# k26_baseboard_dp.net
KiCad netlist of a schematic drawn in Altium Designer
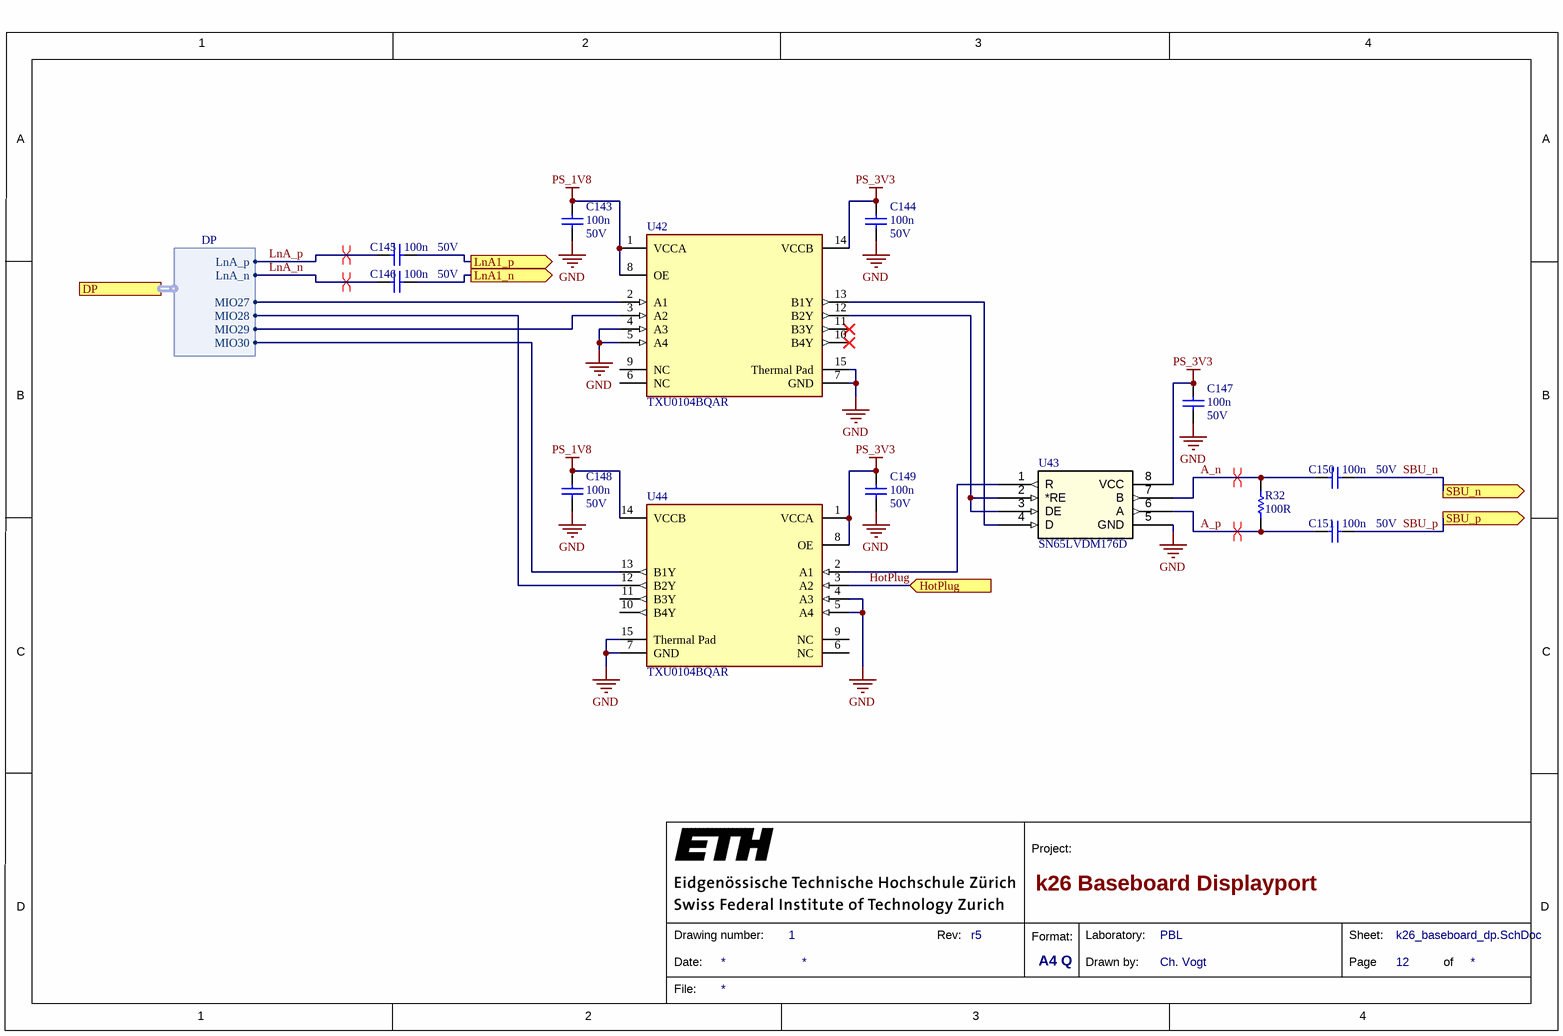
[diagram p0: k26_baseboard_dp.SchDoc]

(export (version "E")
  (design (tool "Eeschema 10.0.6"))
  (components
    (comp (ref "C143")
      (value "100n")
      (footprint "k26_FPGA_drone_baseboard:CAPC0402")
      (fields
        (field (name "MANUFACTURER") "Yageo")
        (field (name "MANUFACTURER PART NUMBER") "CC0402KRX5R9BB104")
        (field (name "RATED DC VOLTAGE (URDC)") "50V")
      )
      (libsource (lib "k26_FPGA_drone_baseboard") (part "cap0402"))
    )
    (comp (ref "C144")
      (value "100n")
      (footprint "k26_FPGA_drone_baseboard:CAPC0402")
      (fields
        (field (name "MANUFACTURER") "Yageo")
        (field (name "MANUFACTURER PART NUMBER") "CC0402KRX5R9BB104")
        (field (name "RATED DC VOLTAGE (URDC)") "50V")
      )
      (libsource (lib "k26_FPGA_drone_baseboard") (part "cap0402"))
    )
    (comp (ref "C145")
      (value "100n")
      (footprint "k26_FPGA_drone_baseboard:CAPC0402")
      (fields
        (field (name "MANUFACTURER") "Yageo")
        (field (name "MANUFACTURER PART NUMBER") "CC0402KRX5R9BB104")
        (field (name "RATED DC VOLTAGE (URDC)") "50V")
      )
      (libsource (lib "k26_FPGA_drone_baseboard") (part "cap0402"))
    )
    (comp (ref "C146")
      (value "100n")
      (footprint "k26_FPGA_drone_baseboard:CAPC0402")
      (fields
        (field (name "MANUFACTURER") "Yageo")
        (field (name "MANUFACTURER PART NUMBER") "CC0402KRX5R9BB104")
        (field (name "RATED DC VOLTAGE (URDC)") "50V")
      )
      (libsource (lib "k26_FPGA_drone_baseboard") (part "cap0402"))
    )
    (comp (ref "C147")
      (value "100n")
      (footprint "k26_FPGA_drone_baseboard:CAPC0402")
      (fields
        (field (name "MANUFACTURER") "Yageo")
        (field (name "MANUFACTURER PART NUMBER") "CC0402KRX5R9BB104")
        (field (name "RATED DC VOLTAGE (URDC)") "50V")
      )
      (libsource (lib "k26_FPGA_drone_baseboard") (part "cap0402"))
    )
    (comp (ref "C148")
      (value "100n")
      (footprint "k26_FPGA_drone_baseboard:CAPC0402")
      (fields
        (field (name "MANUFACTURER") "Yageo")
        (field (name "MANUFACTURER PART NUMBER") "CC0402KRX5R9BB104")
        (field (name "RATED DC VOLTAGE (URDC)") "50V")
      )
      (libsource (lib "k26_FPGA_drone_baseboard") (part "cap0402"))
    )
    (comp (ref "C149")
      (value "100n")
      (footprint "k26_FPGA_drone_baseboard:CAPC0402")
      (fields
        (field (name "MANUFACTURER") "Yageo")
        (field (name "MANUFACTURER PART NUMBER") "CC0402KRX5R9BB104")
        (field (name "RATED DC VOLTAGE (URDC)") "50V")
      )
      (libsource (lib "k26_FPGA_drone_baseboard") (part "cap0402"))
    )
    (comp (ref "C150")
      (value "100n")
      (footprint "k26_FPGA_drone_baseboard:CAPC0402")
      (fields
        (field (name "MANUFACTURER") "Yageo")
        (field (name "MANUFACTURER PART NUMBER") "CC0402KRX5R9BB104")
        (field (name "RATED DC VOLTAGE (URDC)") "50V")
      )
      (libsource (lib "k26_FPGA_drone_baseboard") (part "cap0402"))
    )
    (comp (ref "C151")
      (value "100n")
      (footprint "k26_FPGA_drone_baseboard:CAPC0402")
      (fields
        (field (name "MANUFACTURER") "Yageo")
        (field (name "MANUFACTURER PART NUMBER") "CC0402KRX5R9BB104")
        (field (name "RATED DC VOLTAGE (URDC)") "50V")
      )
      (libsource (lib "k26_FPGA_drone_baseboard") (part "cap0402"))
    )
    (comp (ref "R32")
      (value "100R")
      (footprint "k26_FPGA_drone_baseboard:RES0402")
      (fields
        (field (name "MANUFACTURER") "Panasonic")
        (field (name "MANUFACTURER PART NUMBER") "ERJ-2RKF1000X")
        (field (name "TOLERANCE") "1%")
      )
      (libsource (lib "k26_FPGA_drone_baseboard") (part "res0402"))
    )
    (comp (ref "U42")
      (value "TXU0104BQAR")
      (footprint "FP-BQA0014A-MFG")
      (description "FOUR CHANNEL UNIDIRECTIONAL LEVE")
      (fields (field (name "MANUFACTURER") "Texas Instruments"))
      (libsource (lib "") (part "CMP-04899-000128-1_1"))
    )
    (comp (ref "U43")
      (value "SN65LVDM176D")
      (footprint "D8")
      (description "No Description Available")
      (fields (field (name "COPYRIGHT") "Copyright (C) 2023 Ultra Librarian. All rights reserved."))
      (libsource (lib "k26_FPGA_drone_baseboard") (part "SN65LVDM176D"))
    )
    (comp (ref "U44")
      (value "TXU0104BQAR")
      (footprint "FP-BQA0014A-MFG")
      (description "FOUR CHANNEL UNIDIRECTIONAL LEVE")
      (fields (field (name "MANUFACTURER") "Texas Instruments"))
      (libsource (lib "k26_FPGA_drone_baseboard") (part "CMP-04899-000128-1"))
    )
  )
  (nets
    (net (code "2") (name "/A_n") (class "Default")
      (node (ref "C150") (pin "2") (pinfunction "2_2") (pintype "passive"))
      (node (ref "R32") (pin "2") (pinfunction "2_2") (pintype "passive"))
      (node (ref "U43") (pin "7") (pinfunction "B_7") (pintype "output"))
    )
    (net (code "3") (name "/A_p") (class "Default")
      (node (ref "C151") (pin "2") (pinfunction "2_2") (pintype "passive"))
      (node (ref "R32") (pin "1") (pinfunction "1_1") (pintype "passive"))
      (node (ref "U43") (pin "6") (pinfunction "A_6") (pintype "output"))
    )
    (net (code "4") (name "/HotPlug") (class "Default")
      (node (ref "U44") (pin "3") (pinfunction "A2_3") (pintype "input"))
    )
    (net (code "5") (name "/LnA1_n") (class "Default")
      (node (ref "C146") (pin "1") (pinfunction "1_1") (pintype "passive"))
    )
    (net (code "6") (name "/LnA1_p") (class "Default")
      (node (ref "C145") (pin "1") (pinfunction "1_1") (pintype "passive"))
    )
    (net (code "7") (name "/LnA_n") (class "Default")
      (node (ref "C146") (pin "2") (pinfunction "2_2") (pintype "passive"))
    )
    (net (code "8") (name "/LnA_p") (class "Default")
      (node (ref "C145") (pin "2") (pinfunction "2_2") (pintype "passive"))
    )
    (net (code "9") (name "/MIO27") (class "Default")
      (node (ref "U42") (pin "2") (pinfunction "A1_2") (pintype "input"))
    )
    (net (code "10") (name "/MIO28") (class "Default")
      (node (ref "U44") (pin "12") (pinfunction "B2Y_12") (pintype "output"))
    )
    (net (code "11") (name "/MIO29") (class "Default")
      (node (ref "U42") (pin "3") (pinfunction "A2_3") (pintype "input"))
    )
    (net (code "12") (name "/MIO30") (class "Default")
      (node (ref "U44") (pin "13") (pinfunction "B1Y_13") (pintype "output"))
    )
    (net (code "13") (name "/SBU_n") (class "Default")
      (node (ref "C150") (pin "1") (pinfunction "1_1") (pintype "passive"))
    )
    (net (code "14") (name "/SBU_p") (class "Default")
      (node (ref "C151") (pin "1") (pinfunction "1_1") (pintype "passive"))
    )
    (net (code "16") (name "GND") (class "Default")
      (node (ref "C143") (pin "1") (pinfunction "1_1") (pintype "passive"))
      (node (ref "C144") (pin "1") (pinfunction "1_1") (pintype "passive"))
      (node (ref "C147") (pin "1") (pinfunction "1_1") (pintype "passive"))
      (node (ref "C148") (pin "1") (pinfunction "1_1") (pintype "passive"))
      (node (ref "C149") (pin "1") (pinfunction "1_1") (pintype "passive"))
      (node (ref "U42") (pin "15") (pinfunction "Thermal_Pad_15") (pintype "power_in"))
      (node (ref "U42") (pin "4") (pinfunction "A3_4") (pintype "input"))
      (node (ref "U42") (pin "5") (pinfunction "A4_5") (pintype "input"))
      (node (ref "U42") (pin "7") (pinfunction "GND_7") (pintype "power_in"))
      (node (ref "U43") (pin "5") (pinfunction "GND_5") (pintype "power_in"))
      (node (ref "U44") (pin "15") (pinfunction "Thermal_Pad_15") (pintype "power_in"))
      (node (ref "U44") (pin "4") (pinfunction "A3_4") (pintype "input"))
      (node (ref "U44") (pin "5") (pinfunction "A4_5") (pintype "input"))
      (node (ref "U44") (pin "7") (pinfunction "GND_7") (pintype "power_in"))
    )
    (net (code "17") (name "Net-(U42-B1Y)") (class "Default")
      (node (ref "U42") (pin "13") (pinfunction "B1Y_13") (pintype "output"))
      (node (ref "U43") (pin "4") (pinfunction "D_4") (pintype "input"))
    )
    (net (code "18") (name "Net-(U42-B2Y)") (class "Default")
      (node (ref "U42") (pin "12") (pinfunction "B2Y_12") (pintype "output"))
      (node (ref "U43") (pin "2") (pinfunction "*RE_2") (pintype "input"))
      (node (ref "U43") (pin "3") (pinfunction "DE_3") (pintype "input"))
    )
    (net (code "19") (name "Net-(U43-R)") (class "Default")
      (node (ref "U43") (pin "1") (pinfunction "R_1") (pintype "output"))
      (node (ref "U44") (pin "2") (pinfunction "A1_2") (pintype "input"))
    )
    (net (code "20") (name "PS_1V8") (class "Default")
      (node (ref "C143") (pin "2") (pinfunction "2_2") (pintype "passive"))
      (node (ref "C148") (pin "2") (pinfunction "2_2") (pintype "passive"))
      (node (ref "U42") (pin "1") (pinfunction "VCCA_1") (pintype "power_in"))
      (node (ref "U42") (pin "8") (pinfunction "OE_8") (pintype "passive"))
      (node (ref "U44") (pin "14") (pinfunction "VCCB_14") (pintype "power_in"))
    )
    (net (code "21") (name "PS_3V3") (class "Default")
      (node (ref "C144") (pin "2") (pinfunction "2_2") (pintype "passive"))
      (node (ref "C147") (pin "2") (pinfunction "2_2") (pintype "passive"))
      (node (ref "C149") (pin "2") (pinfunction "2_2") (pintype "passive"))
      (node (ref "U42") (pin "14") (pinfunction "VCCB_14") (pintype "power_in"))
      (node (ref "U43") (pin "8") (pinfunction "VCC_8") (pintype "power_in"))
      (node (ref "U44") (pin "1") (pinfunction "VCCA_1") (pintype "power_in"))
      (node (ref "U44") (pin "8") (pinfunction "OE_8") (pintype "passive"))
    )
    (net (code "22") (name "unconnected-(U42-B3Y-Pad11)") (class "Default")
      (node (ref "U42") (pin "11") (pinfunction "B3Y_11") (pintype "output+no_connect"))
    )
    (net (code "23") (name "unconnected-(U42-B4Y-Pad10)") (class "Default")
      (node (ref "U42") (pin "10") (pinfunction "B4Y_10") (pintype "output+no_connect"))
    )
    (net (code "24") (name "unconnected-(U42-NC-Pad6)") (class "Default")
      (node (ref "U42") (pin "6") (pinfunction "NC_6") (pintype "passive"))
    )
    (net (code "25") (name "unconnected-(U42-NC-Pad9)") (class "Default")
      (node (ref "U42") (pin "9") (pinfunction "NC_9") (pintype "passive"))
    )
    (net (code "26") (name "unconnected-(U44-B3Y-Pad11)") (class "Default")
      (node (ref "U44") (pin "11") (pinfunction "B3Y_11") (pintype "output"))
    )
    (net (code "27") (name "unconnected-(U44-B4Y-Pad10)") (class "Default")
      (node (ref "U44") (pin "10") (pinfunction "B4Y_10") (pintype "output"))
    )
    (net (code "28") (name "unconnected-(U44-NC-Pad6)") (class "Default")
      (node (ref "U44") (pin "6") (pinfunction "NC_6") (pintype "passive"))
    )
    (net (code "29") (name "unconnected-(U44-NC-Pad9)") (class "Default")
      (node (ref "U44") (pin "9") (pinfunction "NC_9") (pintype "passive"))
    )
  )
)
